# CANTransceiver.net
KiCad netlist of a schematic drawn in Altium Designer
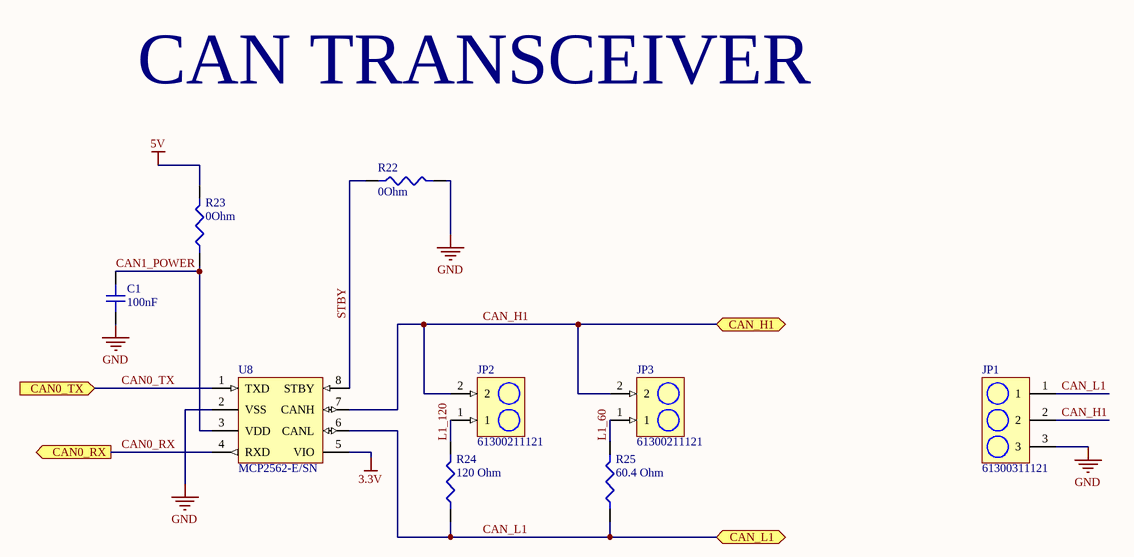
[diagram p0: CANTransceiver.SchDoc]

(export (version "E")
  (design (tool "Eeschema 10.0.6"))
  (components
    (comp (ref "C1")
      (value "100nF")
      (footprint "CAPC1608X10N")
      (description "Cap Ceramic 0.1uF 16V X7R 10% SMD 0603 125C Paper T/R")
      (fields
        (field (name "MANUFACTURER") "KEMET")
        (field (name "MANUFACTURER PART NUMBER") "C0603C104K4RAC7411")
      )
      (libsource (lib "Dashboard") (part "C0603C104K4RAC7411"))
    )
    (comp (ref "JP1")
      (value "61300311121")
      (footprint "61300311121")
      (description "WURTH ELEKTRONIK - 61300311121 - HEADER, 2.54MM, PIN, THT, VERTICAL, 3WAY")
      (fields (field (name "MANUFACTURER") "Wurth Electronics"))
      (libsource (lib "Dashboard") (part "61300311121"))
    )
    (comp (ref "JP2")
      (value "61300211121")
      (footprint "61300211121")
      (description "Headers & Wire Housings WR-PHD 2.54mm 2Pin THT Header")
      (fields (field (name "MANUFACTURER") "Wurth Electronics"))
      (libsource (lib "Dashboard") (part "61300211121"))
    )
    (comp (ref "JP3")
      (value "61300211121")
      (footprint "61300211121")
      (description "Headers & Wire Housings WR-PHD 2.54mm 2Pin THT Header")
      (fields (field (name "MANUFACTURER") "Wurth Electronics"))
      (libsource (lib "Dashboard") (part "61300211121"))
    )
    (comp (ref "R22")
      (value "0Ohm")
      (footprint "RES-0603")
      (description "RES SMD 0 OHM JUMPER 1/10W 0603")
      (fields
        (field (name "MANUFACTURER") "Yageo")
        (field (name "MANUFACTURER PART NUMBER") "RC0603JR-070RL")
      )
      (libsource (lib "Dashboard") (part "RC0603JR-070RL"))
    )
    (comp (ref "R23")
      (value "0Ohm")
      (footprint "RES-0603")
      (description "RES SMD 0 OHM JUMPER 1/10W 0603")
      (fields
        (field (name "MANUFACTURER") "Yageo")
        (field (name "MANUFACTURER PART NUMBER") "RC0603JR-070RL")
      )
      (libsource (lib "Dashboard") (part "RC0603JR-070RL"))
    )
    (comp (ref "R24")
      (value "120 Ohm")
      (footprint "RESC1608X06N")
      (description "Metal film resistor 120 Ω SMD 0603 0.1 W")
      (fields
        (field (name "MANUFACTURER") "Panasonic")
        (field (name "MANUFACTURER PART NUMBER") "ERA-3AEB121V")
      )
      (libsource (lib "Dashboard") (part "ERA-3AEB121V"))
    )
    (comp (ref "R25")
      (value "60.4 Ohm")
      (footprint "60.4 OHM RES 0603")
      (description "RES 60.4 OHM 1% 1/10W 0603")
      (fields
        (field (name "MANUFACTURER") "Stackpole Electronics")
        (field (name "MANUFACTURER PART NUMBER") "RMCF0603FT60R4")
      )
      (libsource (lib "Dashboard") (part "RMCF0603FT60R4"))
    )
    (comp (ref "U8")
      (value "MCP2562-E/SN")
      (footprint "SOIC127P600X175-8N")
      (description "Interface IC CAN SO-8")
      (fields (field (name "MANUFACTURER") "Microchip"))
      (libsource (lib "Dashboard") (part "MCP2562-E/SN"))
    )
  )
  (nets
    (net (code "1") (name "/CAN0_RX") (class "Default")
      (node (ref "U8") (pin "4") (pinfunction "RXD_4") (pintype "output"))
    )
    (net (code "2") (name "/CAN0_TX") (class "Default")
      (node (ref "U8") (pin "1") (pinfunction "TXD_1") (pintype "input"))
    )
    (net (code "3") (name "/CAN1_POWER") (class "Default")
      (node (ref "C1") (pin "2") (pinfunction "2_2") (pintype "passive"))
      (node (ref "R23") (pin "1") (pinfunction "1_1") (pintype "passive"))
      (node (ref "U8") (pin "3") (pinfunction "VDD_3") (pintype "power_in"))
    )
    (net (code "4") (name "/CAN_H1") (class "Default")
      (node (ref "JP1") (pin "2") (pinfunction "2_2") (pintype "passive"))
      (node (ref "JP2") (pin "2") (pinfunction "2_2") (pintype "input"))
      (node (ref "JP3") (pin "2") (pinfunction "2_2") (pintype "input"))
      (node (ref "U8") (pin "7") (pinfunction "CANH_7") (pintype "bidirectional"))
    )
    (net (code "5") (name "/CAN_L1") (class "Default")
      (node (ref "JP1") (pin "1") (pinfunction "1_1") (pintype "passive"))
      (node (ref "R24") (pin "1") (pinfunction "1_1") (pintype "passive"))
      (node (ref "R25") (pin "1") (pinfunction "1_1") (pintype "passive"))
      (node (ref "U8") (pin "6") (pinfunction "CANL_6") (pintype "bidirectional"))
    )
    (net (code "6") (name "/L1_60") (class "Default")
      (node (ref "JP3") (pin "1") (pinfunction "1_1") (pintype "input"))
      (node (ref "R25") (pin "2") (pinfunction "2_2") (pintype "passive"))
    )
    (net (code "7") (name "/L1_120") (class "Default")
      (node (ref "JP2") (pin "1") (pinfunction "1_1") (pintype "input"))
      (node (ref "R24") (pin "2") (pinfunction "2_2") (pintype "passive"))
    )
    (net (code "8") (name "/STBY") (class "Default")
      (node (ref "R22") (pin "1") (pinfunction "1_1") (pintype "passive"))
      (node (ref "U8") (pin "8") (pinfunction "STBY_8") (pintype "input"))
    )
    (net (code "9") (name "3.3V") (class "Default")
      (node (ref "U8") (pin "5") (pinfunction "VIO_5") (pintype "passive"))
    )
    (net (code "10") (name "5V") (class "Default")
      (node (ref "R23") (pin "2") (pinfunction "2_2") (pintype "passive"))
    )
    (net (code "11") (name "GND") (class "Default")
      (node (ref "C1") (pin "1") (pinfunction "1_1") (pintype "passive"))
      (node (ref "JP1") (pin "3") (pinfunction "3_3") (pintype "passive"))
      (node (ref "R22") (pin "2") (pinfunction "2_2") (pintype "passive"))
      (node (ref "U8") (pin "2") (pinfunction "VSS_2") (pintype "power_in"))
    )
  )
)
